# PCB_DIY_SQM_Test_RAW.net
KiCad netlist of a schematic drawn in EAGLE
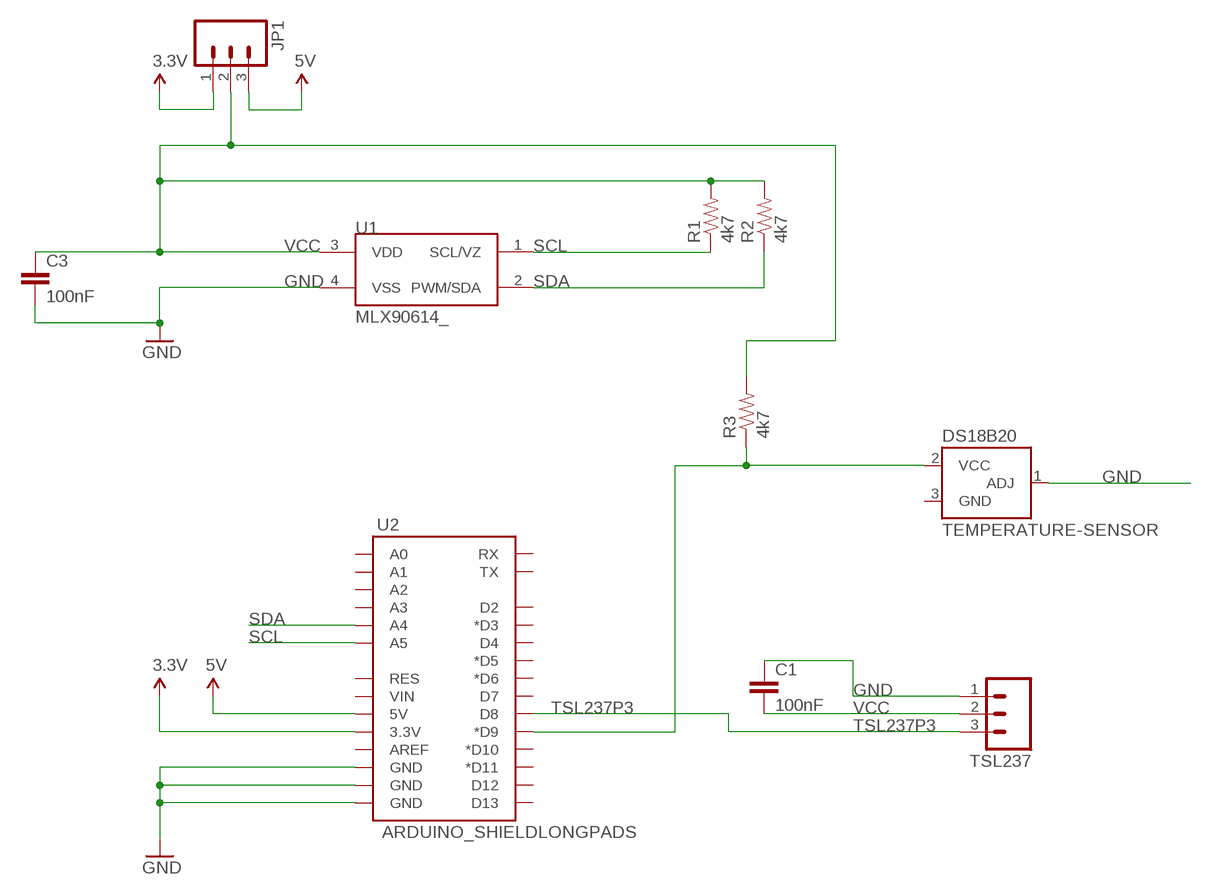
[diagram p0: schematic, sheet 1]

(export (version "E")
  (design (tool "Eeschema 10.0.6"))
  (components
    (comp (ref "C1")
      (value "100nF")
      (footprint "eagle-import:CAP-PTH-SMALL")
      (libsource (lib "eagle-import") (part "CAPPTH"))
    )
    (comp (ref "C3")
      (value "100nF")
      (footprint "eagle-import:CAP-PTH-SMALL")
      (libsource (lib "eagle-import") (part "CAPPTH"))
    )
    (comp (ref "DS18B20")
      (value "TEMPERATURE-SENSOR")
      (footprint "eagle-import:TO-92")
      (libsource (lib "eagle-import") (part "TEMPERATURE-SENSOR"))
    )
    (comp (ref "JP1")
      (value "M03LOCK_LONGPADS")
      (footprint "eagle-import:1X03_LOCK_LONGPADS")
      (libsource (lib "eagle-import") (part "M03LOCK_LONGPADS"))
    )
    (comp (ref "R1")
      (value "4k7")
      (footprint "eagle-import:AXIAL-0.4")
      (libsource (lib "eagle-import") (part "RESISTORPTH-1/4W"))
    )
    (comp (ref "R2")
      (value "4k7")
      (footprint "eagle-import:AXIAL-0.4")
      (libsource (lib "eagle-import") (part "RESISTORPTH-1/4W"))
    )
    (comp (ref "R3")
      (value "4k7")
      (footprint "eagle-import:AXIAL-0.4")
      (libsource (lib "eagle-import") (part "RESISTORPTH-1/4W"))
    )
    (comp (ref "TSL237")
      (value "M03LOCK_LONGPADS")
      (footprint "eagle-import:1X03_LOCK_LONGPADS")
      (libsource (lib "eagle-import") (part "M03LOCK_LONGPADS"))
    )
    (comp (ref "U1")
      (value "MLX90614_")
      (footprint "eagle-import:TO-39")
      (libsource (lib "eagle-import") (part "MLX90614_"))
    )
    (comp (ref "U2")
      (value "ARDUINO_SHIELDLONGPADS")
      (footprint "eagle-import:DUEMILANOVE_SHIELD_LONGPADS")
      (libsource (lib "eagle-import") (part "ARDUINO_SHIELDLONGPADS"))
    )
  )
  (nets
    (net (code "1") (name "/SCL") (class "Default")
      (node (ref "R1") (pin "P$1") (pinfunction "1_P$1") (pintype "passive"))
      (node (ref "U1") (pin "1") (pinfunction "SCL/VZ_1") (pintype "bidirectional"))
      (node (ref "U2") (pin "A5") (pinfunction "A5_A5") (pintype "bidirectional"))
    )
    (net (code "2") (name "/SDA") (class "Default")
      (node (ref "R2") (pin "P$1") (pinfunction "1_P$1") (pintype "passive"))
      (node (ref "U1") (pin "2") (pinfunction "PWM/SDA_2") (pintype "bidirectional"))
      (node (ref "U2") (pin "A4") (pinfunction "A4_A4") (pintype "bidirectional"))
    )
    (net (code "3") (name "/TSL237P3") (class "Default")
      (node (ref "TSL237") (pin "3") (pinfunction "3_3") (pintype "passive"))
      (node (ref "U2") (pin "D8") (pinfunction "D8_D8") (pintype "bidirectional"))
    )
    (net (code "4") (name "/VCC") (class "Default")
      (node (ref "C1") (pin "2") (pinfunction "2_2") (pintype "passive"))
      (node (ref "C3") (pin "1") (pinfunction "1_1") (pintype "passive"))
      (node (ref "JP1") (pin "2") (pinfunction "2_2") (pintype "passive"))
      (node (ref "R1") (pin "P$2") (pinfunction "2_P$2") (pintype "passive"))
      (node (ref "R2") (pin "P$2") (pinfunction "2_P$2") (pintype "passive"))
      (node (ref "R3") (pin "P$2") (pinfunction "2_P$2") (pintype "passive"))
      (node (ref "TSL237") (pin "2") (pinfunction "2_2") (pintype "passive"))
      (node (ref "U1") (pin "3") (pinfunction "VDD_3") (pintype "bidirectional"))
    )
    (net (code "5") (name "3.3V") (class "Default")
      (node (ref "JP1") (pin "1") (pinfunction "1_1") (pintype "passive"))
      (node (ref "U2") (pin "3.3V") (pinfunction "3.3V_3.3V") (pintype "bidirectional"))
    )
    (net (code "6") (name "5V") (class "Default")
      (node (ref "JP1") (pin "3") (pinfunction "3_3") (pintype "passive"))
      (node (ref "U2") (pin "5V") (pinfunction "5V_5V") (pintype "bidirectional"))
    )
    (net (code "7") (name "GND") (class "Default")
      (node (ref "C1") (pin "1") (pinfunction "1_1") (pintype "passive"))
      (node (ref "C3") (pin "2") (pinfunction "2_2") (pintype "passive"))
      (node (ref "DS18B20") (pin "1") (pinfunction "ADJ_1") (pintype "bidirectional"))
      (node (ref "TSL237") (pin "1") (pinfunction "1_1") (pintype "passive"))
      (node (ref "U1") (pin "4") (pinfunction "VSS_4") (pintype "bidirectional"))
      (node (ref "U2") (pin "GND@0") (pinfunction "GND_GND@0") (pintype "bidirectional"))
      (node (ref "U2") (pin "GND@1") (pinfunction "GND_GND@1") (pintype "bidirectional"))
      (node (ref "U2") (pin "GND@2") (pinfunction "GND_GND@2") (pintype "bidirectional"))
    )
    (net (code "8") (name "Net-(DS18B20-VCC)") (class "Default")
      (node (ref "DS18B20") (pin "2") (pinfunction "VCC_2") (pintype "bidirectional"))
      (node (ref "R3") (pin "P$1") (pinfunction "1_P$1") (pintype "passive"))
      (node (ref "U2") (pin "D9") (pinfunction "*D9_D9") (pintype "bidirectional"))
    )
    (net (code "9") (name "unconnected-(DS18B20-GND-Pad3)") (class "Default")
      (node (ref "DS18B20") (pin "3") (pinfunction "GND_3") (pintype "bidirectional"))
    )
    (net (code "10") (name "unconnected-(U2-*D3-PadD3)") (class "Default")
      (node (ref "U2") (pin "D3") (pinfunction "*D3_D3") (pintype "bidirectional"))
    )
    (net (code "11") (name "unconnected-(U2-*D5-PadD5)") (class "Default")
      (node (ref "U2") (pin "D5") (pinfunction "*D5_D5") (pintype "bidirectional"))
    )
    (net (code "12") (name "unconnected-(U2-*D6-PadD6)") (class "Default")
      (node (ref "U2") (pin "D6") (pinfunction "*D6_D6") (pintype "bidirectional"))
    )
    (net (code "13") (name "unconnected-(U2-*D10-PadD10)") (class "Default")
      (node (ref "U2") (pin "D10") (pinfunction "*D10_D10") (pintype "bidirectional"))
    )
    (net (code "14") (name "unconnected-(U2-*D11-PadD11)") (class "Default")
      (node (ref "U2") (pin "D11") (pinfunction "*D11_D11") (pintype "bidirectional"))
    )
    (net (code "15") (name "unconnected-(U2-PadA0)") (class "Default")
      (node (ref "U2") (pin "A0") (pinfunction "A0_A0") (pintype "bidirectional"))
    )
    (net (code "16") (name "unconnected-(U2-PadA1)") (class "Default")
      (node (ref "U2") (pin "A1") (pinfunction "A1_A1") (pintype "bidirectional"))
    )
    (net (code "17") (name "unconnected-(U2-PadA2)") (class "Default")
      (node (ref "U2") (pin "A2") (pinfunction "A2_A2") (pintype "bidirectional"))
    )
    (net (code "18") (name "unconnected-(U2-PadA3)") (class "Default")
      (node (ref "U2") (pin "A3") (pinfunction "A3_A3") (pintype "bidirectional"))
    )
    (net (code "19") (name "unconnected-(U2-PadAREF)") (class "Default")
      (node (ref "U2") (pin "AREF") (pinfunction "AREF_AREF") (pintype "bidirectional"))
    )
    (net (code "20") (name "unconnected-(U2-PadD2)") (class "Default")
      (node (ref "U2") (pin "D2") (pinfunction "D2_D2") (pintype "bidirectional"))
    )
    (net (code "21") (name "unconnected-(U2-PadD4)") (class "Default")
      (node (ref "U2") (pin "D4") (pinfunction "D4_D4") (pintype "bidirectional"))
    )
    (net (code "22") (name "unconnected-(U2-PadD7)") (class "Default")
      (node (ref "U2") (pin "D7") (pinfunction "D7_D7") (pintype "bidirectional"))
    )
    (net (code "23") (name "unconnected-(U2-PadD12)") (class "Default")
      (node (ref "U2") (pin "D12") (pinfunction "D12_D12") (pintype "bidirectional"))
    )
    (net (code "24") (name "unconnected-(U2-PadD13)") (class "Default")
      (node (ref "U2") (pin "D13") (pinfunction "D13_D13") (pintype "bidirectional"))
    )
    (net (code "25") (name "unconnected-(U2-PadRES)") (class "Default")
      (node (ref "U2") (pin "RES") (pinfunction "RES_RES") (pintype "bidirectional"))
    )
    (net (code "26") (name "unconnected-(U2-PadRX)") (class "Default")
      (node (ref "U2") (pin "RX") (pinfunction "RX_RX") (pintype "bidirectional"))
    )
    (net (code "27") (name "unconnected-(U2-PadTX)") (class "Default")
      (node (ref "U2") (pin "TX") (pinfunction "TX_TX") (pintype "bidirectional"))
    )
    (net (code "28") (name "unconnected-(U2-PadVIN)") (class "Default")
      (node (ref "U2") (pin "VIN") (pinfunction "VIN_VIN") (pintype "bidirectional"))
    )
  )
)
